# -V1.net
KiCad netlist of a schematic drawn in Altium Designer
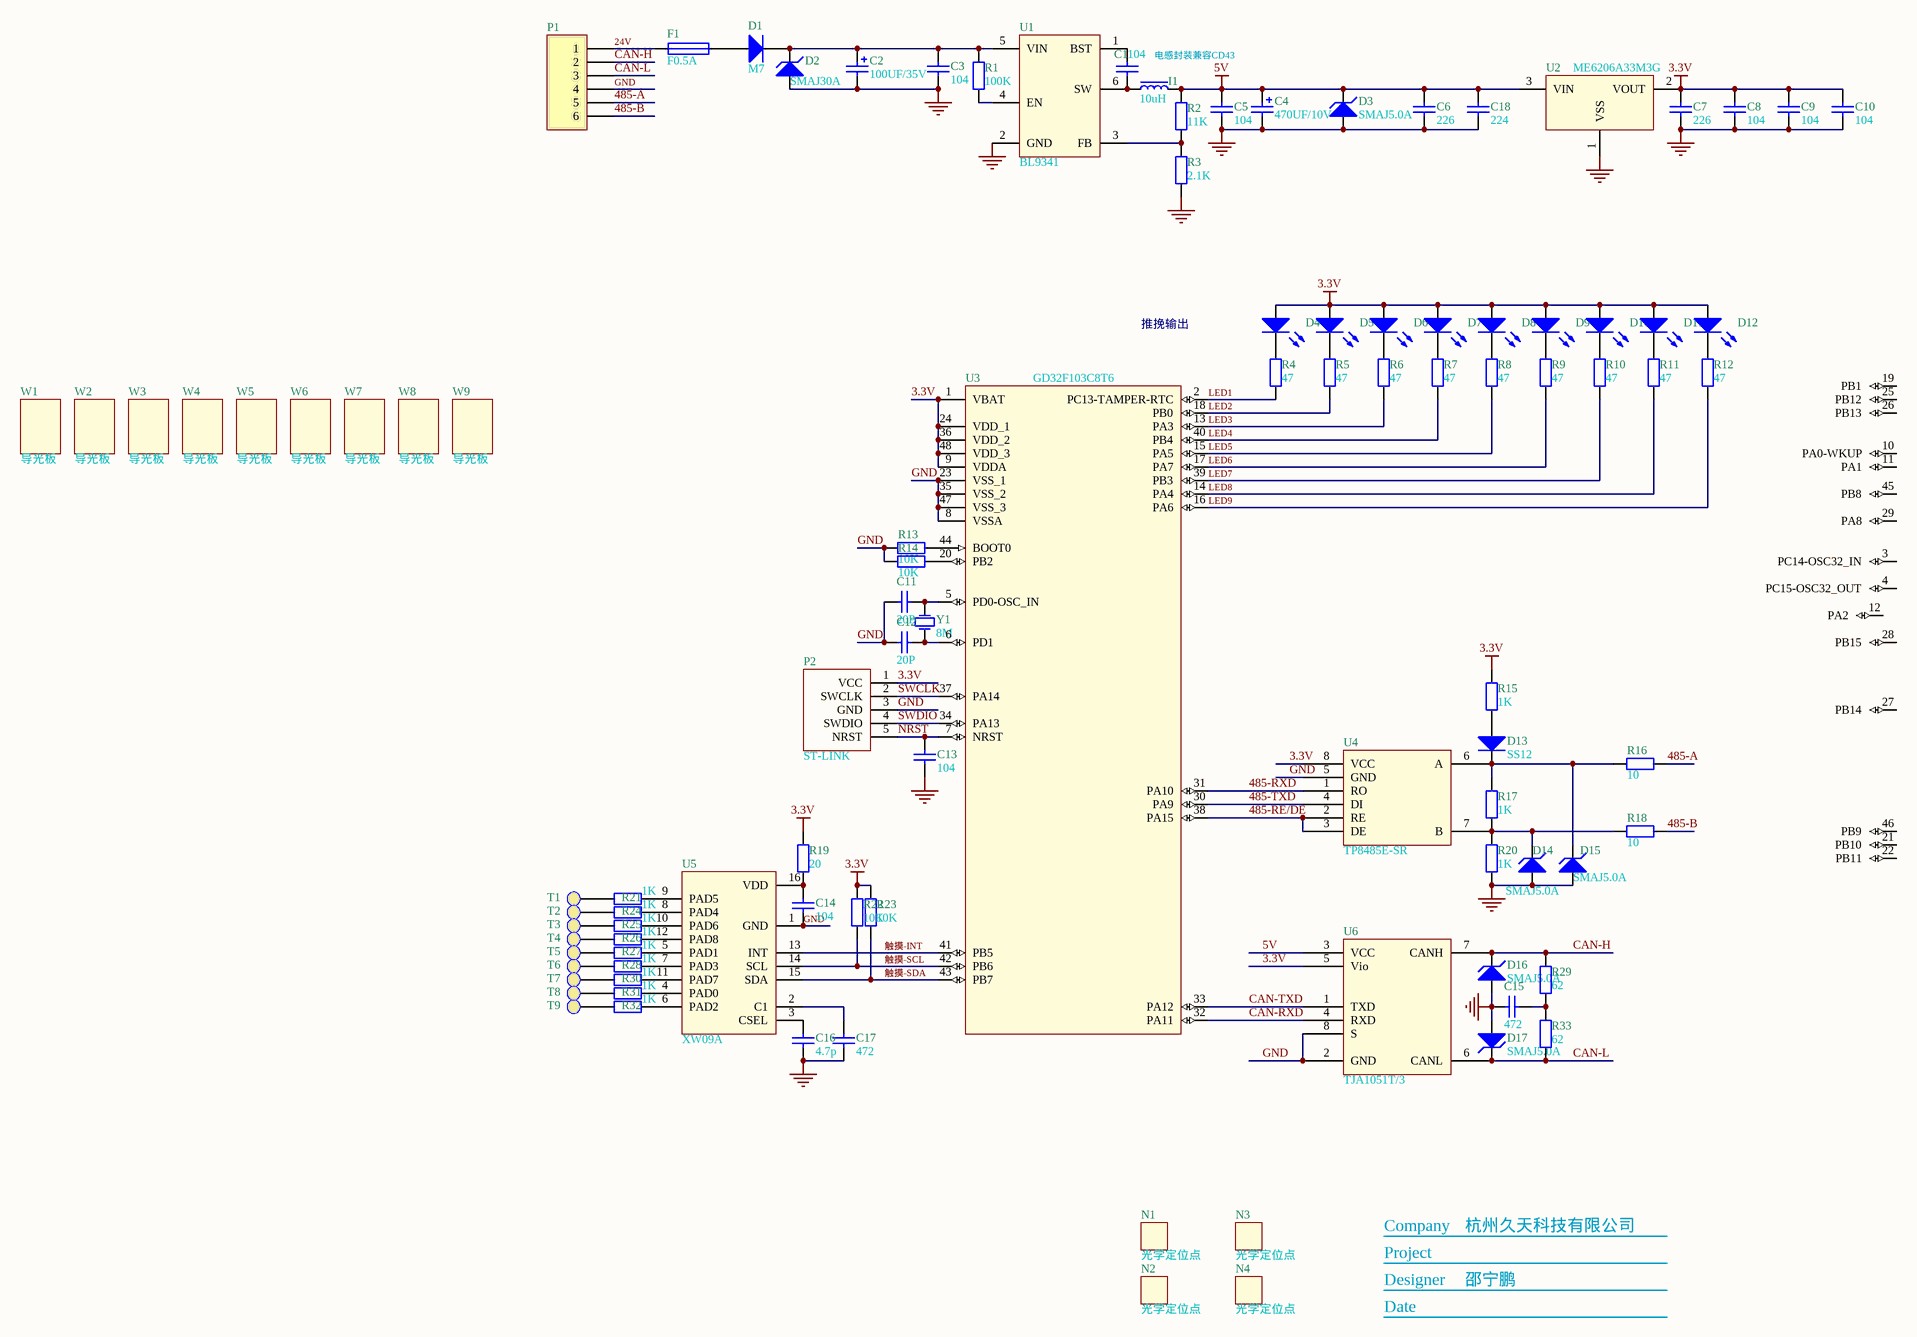
[diagram p0: 九键触摸面板-V1.SchDoc]

(export (version "E")
  (design (tool "Eeschema 10.0.6"))
  (components
    (comp (ref "C1")
      (value "104")
      (footprint "C-0603")
      (description "Capacitor")
      (fields (field (name "PUBLISHER") "Altium Limited"))
      (libsource (lib "元件2.0") (part "Cap"))
    )
    (comp (ref "C2")
      (value "100UF/35V")
      (footprint "贴片固态电容6.3*7.7")
      (description "Polarized Capacitor (Radial)")
      (fields (field (name "PUBLISHER") "Altium Limited"))
      (libsource (lib "元件2.0") (part "Cap Pol1"))
    )
    (comp (ref "C3")
      (value "104")
      (footprint "C-0603")
      (description "Capacitor")
      (fields (field (name "PUBLISHER") "Altium Limited"))
      (libsource (lib "元件2.0") (part "Cap"))
    )
    (comp (ref "C4")
      (value "470UF/10V")
      (footprint "贴片固态电容6.3*7.7")
      (description "Polarized Capacitor (Radial)")
      (fields (field (name "PUBLISHER") "Altium Limited"))
      (libsource (lib "元件2.0") (part "Cap Pol1"))
    )
    (comp (ref "C5")
      (value "104")
      (footprint "C-0603")
      (description "Capacitor")
      (fields (field (name "PUBLISHER") "Altium Limited"))
      (libsource (lib "元件2.0") (part "Cap"))
    )
    (comp (ref "C6")
      (value "226")
      (footprint "C-0603")
      (description "Capacitor")
      (fields (field (name "PUBLISHER") "Altium Limited"))
      (libsource (lib "元件2.0") (part "Cap"))
    )
    (comp (ref "C7")
      (value "226")
      (footprint "C-0603")
      (description "Capacitor")
      (fields (field (name "PUBLISHER") "Altium Limited"))
      (libsource (lib "元件2.0") (part "Cap"))
    )
    (comp (ref "C8")
      (value "104")
      (footprint "C-0603")
      (description "Capacitor")
      (fields (field (name "PUBLISHER") "Altium Limited"))
      (libsource (lib "元件2.0") (part "Cap"))
    )
    (comp (ref "C9")
      (value "104")
      (footprint "C-0603")
      (description "Capacitor")
      (fields (field (name "PUBLISHER") "Altium Limited"))
      (libsource (lib "元件2.0") (part "Cap"))
    )
    (comp (ref "C10")
      (value "104")
      (footprint "C-0603")
      (description "Capacitor")
      (fields (field (name "PUBLISHER") "Altium Limited"))
      (libsource (lib "元件2.0") (part "Cap"))
    )
    (comp (ref "C11")
      (value "20P")
      (footprint "C-0603")
      (description "0805")
      (fields (field (name "PUBLISHER") "Altium Limited"))
      (libsource (lib "2电容-V1.0") (part "Cap-0603"))
    )
    (comp (ref "C12")
      (value "20P")
      (footprint "C-0603")
      (description "0805")
      (fields (field (name "PUBLISHER") "Altium Limited"))
      (libsource (lib "2电容-V1.0") (part "Cap-0603"))
    )
    (comp (ref "C13")
      (value "104")
      (footprint "C-0603")
      (description "0805")
      (fields (field (name "PUBLISHER") "Altium Limited"))
      (libsource (lib "2电容-V1.0") (part "Cap-0603"))
    )
    (comp (ref "C14")
      (value "104")
      (footprint "C-0603")
      (description "0805")
      (fields (field (name "PUBLISHER") "Altium Limited"))
      (libsource (lib "2电容-V1.0") (part "Cap-0603"))
    )
    (comp (ref "C15")
      (value "472")
      (footprint "C-0603")
      (description "0805")
      (fields (field (name "PUBLISHER") "Altium Limited"))
      (libsource (lib "2电容-V1.0") (part "Cap-0603"))
    )
    (comp (ref "C16")
      (value "4.7p")
      (footprint "C-0603")
      (description "0805")
      (fields (field (name "PUBLISHER") "Altium Limited"))
      (libsource (lib "2电容-V1.0") (part "Cap-0603"))
    )
    (comp (ref "C17")
      (value "472")
      (footprint "C-0603")
      (description "0805")
      (fields (field (name "PUBLISHER") "Altium Limited"))
      (libsource (lib "2电容-V1.0") (part "Cap-0603"))
    )
    (comp (ref "C18")
      (value "224")
      (footprint "C-0603")
      (description "Capacitor")
      (fields (field (name "PUBLISHER") "Altium Limited"))
      (libsource (lib "元件2.0") (part "Cap"))
    )
    (comp (ref "D1")
      (value "M7")
      (footprint "SMA")
      (description "SMA")
      (fields (field (name "PUBLISHER") "Altium Limited"))
      (libsource (lib "4二极管-V1.1") (part "M7"))
    )
    (comp (ref "D2")
      (value "SMAJ30A")
      (footprint "SMA")
      (description "SMB")
      (libsource (lib "4二极管-V1.1") (part "TVS-1"))
    )
    (comp (ref "D3")
      (value "SMAJ5.0A")
      (footprint "SMA")
      (description "SMB")
      (libsource (lib "4二极管-V1.1") (part "TVS-1"))
    )
    (comp (ref "D4")
      (value "~")
      (footprint "LED-335侧面绿色-M")
      (fields (field (name "PUBLISHER") "Altium Limited"))
      (libsource (lib "4二极管-V1.1") (part "LED-0603-Blue"))
    )
    (comp (ref "D5")
      (value "~")
      (footprint "LED-335侧面绿色-M")
      (fields (field (name "PUBLISHER") "Altium Limited"))
      (libsource (lib "4二极管-V1.1") (part "LED-0603-Blue"))
    )
    (comp (ref "D6")
      (value "~")
      (footprint "LED-335侧面绿色-M")
      (fields (field (name "PUBLISHER") "Altium Limited"))
      (libsource (lib "4二极管-V1.1") (part "LED-0603-Blue"))
    )
    (comp (ref "D7")
      (value "~")
      (footprint "LED-335侧面绿色-M")
      (fields (field (name "PUBLISHER") "Altium Limited"))
      (libsource (lib "4二极管-V1.1") (part "LED-0603-Blue"))
    )
    (comp (ref "D8")
      (value "~")
      (footprint "LED-335侧面绿色-M")
      (fields (field (name "PUBLISHER") "Altium Limited"))
      (libsource (lib "4二极管-V1.1") (part "LED-0603-Blue"))
    )
    (comp (ref "D9")
      (value "~")
      (footprint "LED-335侧面绿色-M")
      (fields (field (name "PUBLISHER") "Altium Limited"))
      (libsource (lib "4二极管-V1.1") (part "LED-0603-Blue"))
    )
    (comp (ref "D10")
      (value "~")
      (footprint "LED-335侧面绿色-M")
      (fields (field (name "PUBLISHER") "Altium Limited"))
      (libsource (lib "4二极管-V1.1") (part "LED-0603-Blue"))
    )
    (comp (ref "D11")
      (value "~")
      (footprint "LED-335侧面绿色-M")
      (fields (field (name "PUBLISHER") "Altium Limited"))
      (libsource (lib "4二极管-V1.1") (part "LED-0603-Blue"))
    )
    (comp (ref "D12")
      (value "~")
      (footprint "LED-335侧面绿色-M")
      (fields (field (name "PUBLISHER") "Altium Limited"))
      (libsource (lib "4二极管-V1.1") (part "LED-0603-Blue"))
    )
    (comp (ref "D13")
      (value "SS12")
      (footprint "SMA")
      (description "SMA")
      (libsource (lib "4二极管-V1.1") (part "SS14"))
    )
    (comp (ref "D14")
      (value "SMAJ5.0A")
      (footprint "SMA")
      (description "SMB")
      (libsource (lib "4二极管-V1.1") (part "TVS-1"))
    )
    (comp (ref "D15")
      (value "SMAJ5.0A")
      (footprint "SMA")
      (description "SMB")
      (libsource (lib "4二极管-V1.1") (part "TVS-1"))
    )
    (comp (ref "D16")
      (value "SMAJ5.0A")
      (footprint "SMA")
      (description "SMB")
      (libsource (lib "4二极管-V1.1") (part "TVS-1"))
    )
    (comp (ref "D17")
      (value "SMAJ5.0A")
      (footprint "SMA")
      (description "SMB")
      (libsource (lib "4二极管-V1.1") (part "TVS-1"))
    )
    (comp (ref "F1")
      (value "F0.5A")
      (footprint "FUSE-1808")
      (description "Fuse")
      (fields (field (name "PUBLISHER") "Altium Limited"))
      (libsource (lib "11其他元件-V1.0") (part "Fuse 1"))
    )
    (comp (ref "I1") (value "10uH") (footprint "4030") (libsource (lib "3电感-V1.0") (part "Inductance3")))
    (comp (ref "N1") (value "光学定位点") (footprint "MARK-1mm-3mm") (libsource (lib "11其他元件-V1.0") (part "无引脚")))
    (comp (ref "N2") (value "光学定位点") (footprint "MARK-1mm-3mm") (libsource (lib "11其他元件-V1.0") (part "无引脚")))
    (comp (ref "N3") (value "光学定位点") (footprint "MARK-1mm-3mm") (libsource (lib "11其他元件-V1.0") (part "无引脚")))
    (comp (ref "N4") (value "光学定位点") (footprint "MARK-1mm-3mm") (libsource (lib "11其他元件-V1.0") (part "无引脚")))
    (comp (ref "P1")
      (value "~")
      (footprint "KF2EDG5.08V-6P-贴片")
      (description "Header, 6-Pin")
      (fields (field (name "PUBLISHER") "Altium Limited"))
      (libsource (lib "5排针-V1.0") (part "Header 6"))
    )
    (comp (ref "P2") (value "ST-LINK") (footprint "5P下载口") (libsource (lib "下载口") (part "ST-LINK-STM32")))
    (comp (ref "R1")
      (value "100K")
      (footprint "R-0603")
      (description "0603")
      (fields (field (name "PUBLISHER") "Altium Limited"))
      (libsource (lib "1电阻-V1.0") (part "Res2-0603"))
    )
    (comp (ref "R2")
      (value "11K")
      (footprint "R-0603")
      (description "0603")
      (fields (field (name "PUBLISHER") "Altium Limited"))
      (libsource (lib "1电阻-V1.0") (part "Res2-0603"))
    )
    (comp (ref "R3")
      (value "2.1K")
      (footprint "R-0603")
      (description "0603")
      (fields (field (name "PUBLISHER") "Altium Limited"))
      (libsource (lib "1电阻-V1.0") (part "Res2-0603"))
    )
    (comp (ref "R4")
      (value "47")
      (footprint "R-0603")
      (description "0603")
      (fields (field (name "PUBLISHER") "Altium Limited"))
      (libsource (lib "") (part "Res2-0603_1"))
    )
    (comp (ref "R5")
      (value "47")
      (footprint "R-0603")
      (description "0603")
      (fields (field (name "PUBLISHER") "Altium Limited"))
      (libsource (lib "") (part "Res2-0603_1"))
    )
    (comp (ref "R6")
      (value "47")
      (footprint "R-0603")
      (description "0603")
      (fields (field (name "PUBLISHER") "Altium Limited"))
      (libsource (lib "") (part "Res2-0603_1"))
    )
    (comp (ref "R7")
      (value "47")
      (footprint "R-0603")
      (description "0603")
      (fields (field (name "PUBLISHER") "Altium Limited"))
      (libsource (lib "") (part "Res2-0603_1"))
    )
    (comp (ref "R8")
      (value "47")
      (footprint "R-0603")
      (description "0603")
      (fields (field (name "PUBLISHER") "Altium Limited"))
      (libsource (lib "") (part "Res2-0603_1"))
    )
    (comp (ref "R9")
      (value "47")
      (footprint "R-0603")
      (description "0603")
      (fields (field (name "PUBLISHER") "Altium Limited"))
      (libsource (lib "") (part "Res2-0603_1"))
    )
    (comp (ref "R10")
      (value "47")
      (footprint "R-0603")
      (description "0603")
      (fields (field (name "PUBLISHER") "Altium Limited"))
      (libsource (lib "") (part "Res2-0603_1"))
    )
    (comp (ref "R11")
      (value "47")
      (footprint "R-0603")
      (description "0603")
      (fields (field (name "PUBLISHER") "Altium Limited"))
      (libsource (lib "") (part "Res2-0603_1"))
    )
    (comp (ref "R12")
      (value "47")
      (footprint "R-0603")
      (description "0603")
      (fields (field (name "PUBLISHER") "Altium Limited"))
      (libsource (lib "") (part "Res2-0603_1"))
    )
    (comp (ref "R13")
      (value "10K")
      (footprint "R-0603")
      (description "0603")
      (fields (field (name "PUBLISHER") "Altium Limited"))
      (libsource (lib "1电阻-V1.0") (part "Res2-0603"))
    )
    (comp (ref "R14")
      (value "10K")
      (footprint "R-0603")
      (description "0603")
      (fields (field (name "PUBLISHER") "Altium Limited"))
      (libsource (lib "1电阻-V1.0") (part "Res2-0603"))
    )
    (comp (ref "R15")
      (value "1K")
      (footprint "R-0603")
      (description "Resistor")
      (fields (field (name "PUBLISHER") "Altium Limited"))
      (libsource (lib "元件2.0") (part "Res2"))
    )
    (comp (ref "R16")
      (value "10")
      (footprint "R-0603")
      (description "Resistor")
      (fields (field (name "PUBLISHER") "Altium Limited"))
      (libsource (lib "Miscellaneous Devices") (part "Res2"))
    )
    (comp (ref "R17")
      (value "1K")
      (footprint "R-1206")
      (description "Resistor")
      (fields (field (name "PUBLISHER") "Altium Limited"))
      (libsource (lib "") (part "Res2_1"))
    )
    (comp (ref "R18")
      (value "10")
      (footprint "R-0603")
      (description "Resistor")
      (fields (field (name "PUBLISHER") "Altium Limited"))
      (libsource (lib "Miscellaneous Devices") (part "Res2"))
    )
    (comp (ref "R19")
      (value "20")
      (footprint "R-0603")
      (description "0603")
      (fields (field (name "PUBLISHER") "Altium Limited"))
      (libsource (lib "") (part "Res2-0603_1"))
    )
    (comp (ref "R20")
      (value "1K")
      (footprint "R-0603")
      (description "Resistor")
      (fields (field (name "PUBLISHER") "Altium Limited"))
      (libsource (lib "") (part "Res2_1"))
    )
    (comp (ref "R21")
      (value "1K")
      (footprint "R-0603")
      (description "0603")
      (fields (field (name "PUBLISHER") "Altium Limited"))
      (libsource (lib "1电阻-V1.0") (part "Res2-0603"))
    )
    (comp (ref "R22")
      (value "10K")
      (footprint "R-0603")
      (description "0603")
      (fields (field (name "PUBLISHER") "Altium Limited"))
      (libsource (lib "") (part "Res2-0603_2"))
    )
    (comp (ref "R23")
      (value "10K")
      (footprint "R-0603")
      (description "0603")
      (fields (field (name "PUBLISHER") "Altium Limited"))
      (libsource (lib "") (part "Res2-0603_2"))
    )
    (comp (ref "R24")
      (value "1K")
      (footprint "R-0603")
      (description "0603")
      (fields (field (name "PUBLISHER") "Altium Limited"))
      (libsource (lib "1电阻-V1.0") (part "Res2-0603"))
    )
    (comp (ref "R25")
      (value "1K")
      (footprint "R-0603")
      (description "0603")
      (fields (field (name "PUBLISHER") "Altium Limited"))
      (libsource (lib "1电阻-V1.0") (part "Res2-0603"))
    )
    (comp (ref "R26")
      (value "1K")
      (footprint "R-0603")
      (description "0603")
      (fields (field (name "PUBLISHER") "Altium Limited"))
      (libsource (lib "1电阻-V1.0") (part "Res2-0603"))
    )
    (comp (ref "R27")
      (value "1K")
      (footprint "R-0603")
      (description "0603")
      (fields (field (name "PUBLISHER") "Altium Limited"))
      (libsource (lib "1电阻-V1.0") (part "Res2-0603"))
    )
    (comp (ref "R28")
      (value "1K")
      (footprint "R-0603")
      (description "0603")
      (fields (field (name "PUBLISHER") "Altium Limited"))
      (libsource (lib "1电阻-V1.0") (part "Res2-0603"))
    )
    (comp (ref "R29")
      (value "62")
      (footprint "R-1206")
      (description "Resistor")
      (fields (field (name "PUBLISHER") "Altium Limited"))
      (libsource (lib "") (part "Res2_1"))
    )
    (comp (ref "R30")
      (value "1K")
      (footprint "R-0603")
      (description "0603")
      (fields (field (name "PUBLISHER") "Altium Limited"))
      (libsource (lib "1电阻-V1.0") (part "Res2-0603"))
    )
    (comp (ref "R31")
      (value "1K")
      (footprint "R-0603")
      (description "0603")
      (fields (field (name "PUBLISHER") "Altium Limited"))
      (libsource (lib "1电阻-V1.0") (part "Res2-0603"))
    )
    (comp (ref "R32")
      (value "1K")
      (footprint "R-0603")
      (description "0603")
      (fields (field (name "PUBLISHER") "Altium Limited"))
      (libsource (lib "1电阻-V1.0") (part "Res2-0603"))
    )
    (comp (ref "R33")
      (value "62")
      (footprint "R-1206")
      (description "Resistor")
      (fields (field (name "PUBLISHER") "Altium Limited"))
      (libsource (lib "") (part "Res2_1"))
    )
    (comp (ref "T1") (value "~") (footprint "焊点1mm") (libsource (lib "11其他元件-V1.0") (part "测试点")))
    (comp (ref "T2") (value "~") (footprint "焊点1mm") (libsource (lib "11其他元件-V1.0") (part "测试点")))
    (comp (ref "T3") (value "~") (footprint "焊点1mm") (libsource (lib "11其他元件-V1.0") (part "测试点")))
    (comp (ref "T4") (value "~") (footprint "焊点1mm") (libsource (lib "11其他元件-V1.0") (part "测试点")))
    (comp (ref "T5") (value "~") (footprint "焊点1mm") (libsource (lib "11其他元件-V1.0") (part "测试点")))
    (comp (ref "T6") (value "~") (footprint "焊点1mm") (libsource (lib "11其他元件-V1.0") (part "测试点")))
    (comp (ref "T7") (value "~") (footprint "焊点1mm") (libsource (lib "11其他元件-V1.0") (part "测试点")))
    (comp (ref "T8") (value "~") (footprint "焊点1mm") (libsource (lib "11其他元件-V1.0") (part "测试点")))
    (comp (ref "T9") (value "~") (footprint "焊点1mm") (libsource (lib "11其他元件-V1.0") (part "测试点")))
    (comp (ref "U1") (value "BL9341") (footprint "SOT-23-6-m") (libsource (lib "电源芯片DC-DC") (part "BL9341")))
    (comp (ref "U2")
      (value "ME6206A33M3G")
      (footprint "SOT-23")
      (description "LDO稳压 SOT-23")
      (libsource (lib "电源芯片-线性稳压-V1") (part "ME6206A33M3G"))
    )
    (comp (ref "U3")
      (value "GD32F103C8T6")
      (footprint "LQFP48-L")
      (libsource (lib "9单片机-V1.0") (part "GD32F103C8T6"))
    )
    (comp (ref "U4")
      (value "TP8485E-SR")
      (footprint "SOP-8-m")
      (description "RS485总线转串口")
      (libsource (lib "集成电路1.0") (part "MAX3082"))
    )
    (comp (ref "U5") (value "XW09A") (footprint "SOP-16-M") (libsource (lib "触摸-V1") (part "XW09A")))
    (comp (ref "U6") (value "TJA1051T/3") (footprint "SOP-8-M") (libsource (lib "通讯-V1") (part "TJA1051T/3")))
    (comp (ref "W1") (value "导光板") (footprint "导光板20.5*15*2") (libsource (lib "11其他元件-V1.0") (part "导光板")))
    (comp (ref "W2") (value "导光板") (footprint "导光板20.5*15*2") (libsource (lib "11其他元件-V1.0") (part "导光板")))
    (comp (ref "W3") (value "导光板") (footprint "导光板20.5*15*2") (libsource (lib "11其他元件-V1.0") (part "导光板")))
    (comp (ref "W4") (value "导光板") (footprint "导光板20.5*15*2") (libsource (lib "11其他元件-V1.0") (part "导光板")))
    (comp (ref "W5") (value "导光板") (footprint "导光板20.5*15*2") (libsource (lib "11其他元件-V1.0") (part "导光板")))
    (comp (ref "W6") (value "导光板") (footprint "导光板20.5*15*2") (libsource (lib "11其他元件-V1.0") (part "导光板")))
    (comp (ref "W7") (value "导光板") (footprint "导光板20.5*15*2") (libsource (lib "11其他元件-V1.0") (part "导光板")))
    (comp (ref "W8") (value "导光板") (footprint "导光板20.5*15*2") (libsource (lib "11其他元件-V1.0") (part "导光板")))
    (comp (ref "W9") (value "导光板") (footprint "导光板20.5*15*2") (libsource (lib "11其他元件-V1.0") (part "导光板")))
    (comp (ref "Y1") (value "8M") (footprint "HC-49SMD") (libsource (lib "11其他元件-V1.0") (part "晶振")))
  )
  (nets
    (net (code "1") (name "/24V") (class "Default")
      (node (ref "F1") (pin "1") (pinfunction "1_1") (pintype "passive"))
      (node (ref "P1") (pin "1") (pinfunction "1_1") (pintype "passive"))
    )
    (net (code "2") (name "/485-A") (class "Default")
      (node (ref "P1") (pin "5") (pinfunction "5_5") (pintype "passive"))
      (node (ref "R16") (pin "1") (pinfunction "1_1") (pintype "passive"))
    )
    (net (code "3") (name "/485-B") (class "Default")
      (node (ref "P1") (pin "6") (pinfunction "6_6") (pintype "passive"))
      (node (ref "R18") (pin "1") (pinfunction "1_1") (pintype "passive"))
    )
    (net (code "4") (name "/485-RE{slash}DE") (class "Default")
      (node (ref "U3") (pin "38") (pinfunction "PA15_38") (pintype "bidirectional"))
      (node (ref "U4") (pin "2") (pinfunction "RE_2") (pintype "passive"))
      (node (ref "U4") (pin "3") (pinfunction "DE_3") (pintype "passive"))
    )
    (net (code "5") (name "/485-RXD") (class "Default")
      (node (ref "U3") (pin "31") (pinfunction "PA10_31") (pintype "bidirectional"))
      (node (ref "U4") (pin "1") (pinfunction "RO_1") (pintype "passive"))
    )
    (net (code "6") (name "/485-TXD") (class "Default")
      (node (ref "U3") (pin "30") (pinfunction "PA9_30") (pintype "bidirectional"))
      (node (ref "U4") (pin "4") (pinfunction "DI_4") (pintype "passive"))
    )
    (net (code "7") (name "/CAN-H") (class "Default")
      (node (ref "D16") (pin "2") (pinfunction "K_2") (pintype "passive"))
      (node (ref "P1") (pin "2") (pinfunction "2_2") (pintype "passive"))
      (node (ref "R29") (pin "1") (pinfunction "1_1") (pintype "passive"))
      (node (ref "U6") (pin "7") (pinfunction "CANH_7") (pintype "passive"))
    )
    (net (code "8") (name "/CAN-L") (class "Default")
      (node (ref "D17") (pin "2") (pinfunction "K_2") (pintype "passive"))
      (node (ref "P1") (pin "3") (pinfunction "3_3") (pintype "passive"))
      (node (ref "R33") (pin "2") (pinfunction "2_2") (pintype "passive"))
      (node (ref "U6") (pin "6") (pinfunction "CANL_6") (pintype "passive"))
    )
    (net (code "9") (name "/CAN-RXD") (class "Default")
      (node (ref "U3") (pin "32") (pinfunction "PA11_32") (pintype "bidirectional"))
      (node (ref "U6") (pin "4") (pinfunction "RXD_4") (pintype "passive"))
    )
    (net (code "10") (name "/CAN-TXD") (class "Default")
      (node (ref "U3") (pin "33") (pinfunction "PA12_33") (pintype "bidirectional"))
      (node (ref "U6") (pin "1") (pinfunction "TXD_1") (pintype "passive"))
    )
    (net (code "11") (name "/LED1") (class "Default")
      (node (ref "R4") (pin "2") (pinfunction "2_2") (pintype "passive"))
      (node (ref "U3") (pin "2") (pinfunction "PC13-TAMPER-RTC_2") (pintype "bidirectional"))
    )
    (net (code "12") (name "/LED2") (class "Default")
      (node (ref "R5") (pin "2") (pinfunction "2_2") (pintype "passive"))
      (node (ref "U3") (pin "18") (pinfunction "PB0_18") (pintype "bidirectional"))
    )
    (net (code "13") (name "/LED3") (class "Default")
      (node (ref "R6") (pin "2") (pinfunction "2_2") (pintype "passive"))
      (node (ref "U3") (pin "13") (pinfunction "PA3_13") (pintype "bidirectional"))
    )
    (net (code "14") (name "/LED4") (class "Default")
      (node (ref "R7") (pin "2") (pinfunction "2_2") (pintype "passive"))
      (node (ref "U3") (pin "40") (pinfunction "PB4_40") (pintype "bidirectional"))
    )
    (net (code "15") (name "/LED5") (class "Default")
      (node (ref "R8") (pin "2") (pinfunction "2_2") (pintype "passive"))
      (node (ref "U3") (pin "15") (pinfunction "PA5_15") (pintype "bidirectional"))
    )
    (net (code "16") (name "/LED6") (class "Default")
      (node (ref "R9") (pin "2") (pinfunction "2_2") (pintype "passive"))
      (node (ref "U3") (pin "17") (pinfunction "PA7_17") (pintype "bidirectional"))
    )
    (net (code "17") (name "/LED7") (class "Default")
      (node (ref "R10") (pin "2") (pinfunction "2_2") (pintype "passive"))
      (node (ref "U3") (pin "39") (pinfunction "PB3_39") (pintype "bidirectional"))
    )
    (net (code "18") (name "/LED8") (class "Default")
      (node (ref "R11") (pin "2") (pinfunction "2_2") (pintype "passive"))
      (node (ref "U3") (pin "14") (pinfunction "PA4_14") (pintype "bidirectional"))
    )
    (net (code "19") (name "/LED9") (class "Default")
      (node (ref "R12") (pin "2") (pinfunction "2_2") (pintype "passive"))
      (node (ref "U3") (pin "16") (pinfunction "PA6_16") (pintype "bidirectional"))
    )
    (net (code "20") (name "/NRST") (class "Default")
      (node (ref "C13") (pin "2") (pinfunction "2_2") (pintype "passive"))
      (node (ref "P2") (pin "5") (pinfunction "NRST_5") (pintype "passive"))
      (node (ref "U3") (pin "7") (pinfunction "NRST_7") (pintype "bidirectional"))
    )
    (net (code "21") (name "/SWCLK") (class "Default")
      (node (ref "P2") (pin "2") (pinfunction "SWCLK_2") (pintype "passive"))
      (node (ref "U3") (pin "37") (pinfunction "PA14_37") (pintype "bidirectional"))
    )
    (net (code "22") (name "/SWDIO") (class "Default")
      (node (ref "P2") (pin "4") (pinfunction "SWDIO_4") (pintype "passive"))
      (node (ref "U3") (pin "34") (pinfunction "PA13_34") (pintype "bidirectional"))
    )
    (net (code "23") (name "/触摸-INT") (class "Default")
      (node (ref "U3") (pin "41") (pinfunction "PB5_41") (pintype "bidirectional"))
      (node (ref "U5") (pin "13") (pinfunction "INT_13") (pintype "passive"))
    )
    (net (code "24") (name "/触摸-SCL") (class "Default")
      (node (ref "R22") (pin "1") (pinfunction "1_1") (pintype "passive"))
      (node (ref "U3") (pin "42") (pinfunction "PB6_42") (pintype "bidirectional"))
      (node (ref "U5") (pin "14") (pinfunction "SCL_14") (pintype "passive"))
    )
    (net (code "25") (name "/触摸-SDA") (class "Default")
      (node (ref "R23") (pin "1") (pinfunction "1_1") (pintype "passive"))
      (node (ref "U3") (pin "43") (pinfunction "PB7_43") (pintype "bidirectional"))
      (node (ref "U5") (pin "15") (pinfunction "SDA_15") (pintype "passive"))
    )
    (net (code "26") (name "3.3V") (class "Default")
      (node (ref "C10") (pin "2") (pinfunction "2_2") (pintype "passive"))
      (node (ref "C7") (pin "2") (pinfunction "2_2") (pintype "passive"))
      (node (ref "C8") (pin "2") (pinfunction "2_2") (pintype "passive"))
      (node (ref "C9") (pin "2") (pinfunction "2_2") (pintype "passive"))
      (node (ref "D10") (pin "1") (pinfunction "A_1") (pintype "passive"))
      (node (ref "D11") (pin "1") (pinfunction "A_1") (pintype "passive"))
      (node (ref "D12") (pin "1") (pinfunction "A_1") (pintype "passive"))
      (node (ref "D4") (pin "1") (pinfunction "A_1") (pintype "passive"))
      (node (ref "D5") (pin "1") (pinfunction "A_1") (pintype "passive"))
      (node (ref "D6") (pin "1") (pinfunction "A_1") (pintype "passive"))
      (node (ref "D7") (pin "1") (pinfunction "A_1") (pintype "passive"))
      (node (ref "D8") (pin "1") (pinfunction "A_1") (pintype "passive"))
      (node (ref "D9") (pin "1") (pinfunction "A_1") (pintype "passive"))
      (node (ref "P2") (pin "1") (pinfunction "VCC_1") (pintype "passive"))
      (node (ref "R15") (pin "1") (pinfunction "1_1") (pintype "passive"))
      (node (ref "R19") (pin "1") (pinfunction "1_1") (pintype "passive"))
      (node (ref "R22") (pin "2") (pinfunction "2_2") (pintype "passive"))
      (node (ref "R23") (pin "2") (pinfunction "2_2") (pintype "passive"))
      (node (ref "U2") (pin "2") (pinfunction "VOUT_2") (pintype "passive"))
      (node (ref "U3") (pin "1") (pinfunction "VBAT_1") (pintype "power_in"))
      (node (ref "U3") (pin "24") (pinfunction "VDD_1_24") (pintype "power_in"))
      (node (ref "U3") (pin "36") (pinfunction "VDD_2_36") (pintype "power_in"))
      (node (ref "U3") (pin "48") (pinfunction "VDD_3_48") (pintype "power_in"))
      (node (ref "U3") (pin "9") (pinfunction "VDDA_9") (pintype "power_in"))
      (node (ref "U4") (pin "8") (pinfunction "VCC_8") (pintype "passive"))
      (node (ref "U6") (pin "5") (pinfunction "Vio_5") (pintype "passive"))
    )
    (net (code "27") (name "5V") (class "Default")
      (node (ref "C18") (pin "2") (pinfunction "2_2") (pintype "passive"))
      (node (ref "C4") (pin "1") (pinfunction "1_1") (pintype "passive"))
      (node (ref "C5") (pin "2") (pinfunction "2_2") (pintype "passive"))
      (node (ref "C6") (pin "2") (pinfunction "2_2") (pintype "passive"))
      (node (ref "D3") (pin "2") (pinfunction "K_2") (pintype "passive"))
      (node (ref "I1") (pin "2") (pinfunction "2_2") (pintype "passive"))
      (node (ref "R2") (pin "1") (pinfunction "1_1") (pintype "passive"))
      (node (ref "U2") (pin "3") (pinfunction "VIN_3") (pintype "passive"))
      (node (ref "U6") (pin "3") (pinfunction "VCC_3") (pintype "passive"))
    )
    (net (code "28") (name "GND") (class "Default")
      (node (ref "C10") (pin "1") (pinfunction "1_1") (pintype "passive"))
      (node (ref "C11") (pin "1") (pinfunction "1_1") (pintype "passive"))
      (node (ref "C12") (pin "1") (pinfunction "1_1") (pintype "passive"))
      (node (ref "C13") (pin "1") (pinfunction "1_1") (pintype "passive"))
      (node (ref "C14") (pin "1") (pinfunction "1_1") (pintype "passive"))
      (node (ref "C15") (pin "1") (pinfunction "1_1") (pintype "passive"))
      (node (ref "C16") (pin "1") (pinfunction "1_1") (pintype "passive"))
      (node (ref "C17") (pin "1") (pinfunction "1_1") (pintype "passive"))
      (node (ref "C18") (pin "1") (pinfunction "1_1") (pintype "passive"))
      (node (ref "C2") (pin "2") (pinfunction "2_2") (pintype "passive"))
      (node (ref "C3") (pin "1") (pinfunction "1_1") (pintype "passive"))
      (node (ref "C4") (pin "2") (pinfunction "2_2") (pintype "passive"))
      (node (ref "C5") (pin "1") (pinfunction "1_1") (pintype "passive"))
      (node (ref "C6") (pin "1") (pinfunction "1_1") (pintype "passive"))
      (node (ref "C7") (pin "1") (pinfunction "1_1") (pintype "passive"))
      (node (ref "C8") (pin "1") (pinfunction "1_1") (pintype "passive"))
      (node (ref "C9") (pin "1") (pinfunction "1_1") (pintype "passive"))
      (node (ref "D14") (pin "1") (pinfunction "A_1") (pintype "passive"))
      (node (ref "D15") (pin "1") (pinfunction "A_1") (pintype "passive"))
      (node (ref "D16") (pin "1") (pinfunction "A_1") (pintype "passive"))
      (node (ref "D17") (pin "1") (pinfunction "A_1") (pintype "passive"))
      (node (ref "D2") (pin "1") (pinfunction "A_1") (pintype "passive"))
      (node (ref "D3") (pin "1") (pinfunction "A_1") (pintype "passive"))
      (node (ref "P1") (pin "4") (pinfunction "4_4") (pintype "passive"))
      (node (ref "P2") (pin "3") (pinfunction "GND_3") (pintype "passive"))
      (node (ref "R13") (pin "2") (pinfunction "2_2") (pintype "passive"))
      (node (ref "R14") (pin "2") (pinfunction "2_2") (pintype "passive"))
      (node (ref "R20") (pin "1") (pinfunction "1_1") (pintype "passive"))
      (node (ref "R3") (pin "2") (pinfunction "2_2") (pintype "passive"))
      (node (ref "U1") (pin "2") (pinfunction "GND_2") (pintype "passive"))
      (node (ref "U2") (pin "1") (pinfunction "VSS_1") (pintype "passive"))
      (node (ref "U3") (pin "23") (pinfunction "VSS_1_23") (pintype "power_in"))
      (node (ref "U3") (pin "35") (pinfunction "VSS_2_35") (pintype "power_in"))
      (node (ref "U3") (pin "47") (pinfunction "VSS_3_47") (pintype "power_in"))
      (node (ref "U3") (pin "8") (pinfunction "VSSA_8") (pintype "power_in"))
      (node (ref "U4") (pin "5") (pinfunction "GND_5") (pintype "passive"))
      (node (ref "U5") (pin "1") (pinfunction "GND_1") (pintype "passive"))
      (node (ref "U6") (pin "2") (pinfunction "GND_2") (pintype "passive"))
      (node (ref "U6") (pin "8") (pinfunction "S_8") (pintype "passive"))
    )
    (net (code "29") (name "Net-(C15-Pad2)") (class "Default")
      (node (ref "C15") (pin "2") (pinfunction "2_2") (pintype "passive"))
      (node (ref "R29") (pin "2") (pinfunction "2_2") (pintype "passive"))
      (node (ref "R33") (pin "1") (pinfunction "1_1") (pintype "passive"))
    )
    (net (code "30") (name "Net-(D1-A)") (class "Default")
      (node (ref "D1") (pin "1") (pinfunction "A_1") (pintype "passive"))
      (node (ref "F1") (pin "2") (pinfunction "2_2") (pintype "passive"))
    )
    (net (code "31") (name "Net-(D1-K)") (class "Default")
      (node (ref "C2") (pin "1") (pinfunction "1_1") (pintype "passive"))
      (node (ref "C3") (pin "2") (pinfunction "2_2") (pintype "passive"))
      (node (ref "D1") (pin "2") (pinfunction "K_2") (pintype "passive"))
      (node (ref "D2") (pin "2") (pinfunction "K_2") (pintype "passive"))
      (node (ref "R1") (pin "1") (pinfunction "1_1") (pintype "passive"))
      (node (ref "U1") (pin "5") (pinfunction "VIN_5") (pintype "passive"))
    )
    (net (code "32") (name "Net-(D4-K)") (class "Default")
      (node (ref "D4") (pin "2") (pinfunction "K_2") (pintype "passive"))
      (node (ref "R4") (pin "1") (pinfunction "1_1") (pintype "passive"))
    )
    (net (code "33") (name "Net-(D5-K)") (class "Default")
      (node (ref "D5") (pin "2") (pinfunction "K_2") (pintype "passive"))
      (node (ref "R5") (pin "1") (pinfunction "1_1") (pintype "passive"))
    )
    (net (code "34") (name "Net-(D6-K)") (class "Default")
      (node (ref "D6") (pin "2") (pinfunction "K_2") (pintype "passive"))
      (node (ref "R6") (pin "1") (pinfunction "1_1") (pintype "passive"))
    )
    (net (code "35") (name "Net-(D7-K)") (class "Default")
      (node (ref "D7") (pin "2") (pinfunction "K_2") (pintype "passive"))
      (node (ref "R7") (pin "1") (pinfunction "1_1") (pintype "passive"))
    )
    (net (code "36") (name "Net-(D8-K)") (class "Default")
      (node (ref "D8") (pin "2") (pinfunction "K_2") (pintype "passive"))
      (node (ref "R8") (pin "1") (pinfunction "1_1") (pintype "passive"))
    )
    (net (code "37") (name "Net-(D9-K)") (class "Default")
      (node (ref "D9") (pin "2") (pinfunction "K_2") (pintype "passive"))
      (node (ref "R9") (pin "1") (pinfunction "1_1") (pintype "passive"))
    )
    (net (code "38") (name "Net-(D10-K)") (class "Default")
      (node (ref "D10") (pin "2") (pinfunction "K_2") (pintype "passive"))
      (node (ref "R10") (pin "1") (pinfunction "1_1") (pintype "passive"))
    )
    (net (code "39") (name "Net-(D11-K)") (class "Default")
      (node (ref "D11") (pin "2") (pinfunction "K_2") (pintype "passive"))
      (node (ref "R11") (pin "1") (pinfunction "1_1") (pintype "passive"))
    )
    (net (code "40") (name "Net-(D12-K)") (class "Default")
      (node (ref "D12") (pin "2") (pinfunction "K_2") (pintype "passive"))
      (node (ref "R12") (pin "1") (pinfunction "1_1") (pintype "passive"))
    )
    (net (code "41") (name "Net-(D13-A)") (class "Default")
      (node (ref "D13") (pin "1") (pinfunction "A_1") (pintype "passive"))
      (node (ref "R15") (pin "2") (pinfunction "2_2") (pintype "passive"))
    )
    (net (code "42") (name "Net-(D13-K)") (class "Default")
      (node (ref "D13") (pin "2") (pinfunction "K_2") (pintype "passive"))
      (node (ref "D15") (pin "2") (pinfunction "K_2") (pintype "passive"))
      (node (ref "R16") (pin "2") (pinfunction "2_2") (pintype "passive"))
      (node (ref "R17") (pin "1") (pinfunction "1_1") (pintype "passive"))
      (node (ref "U4") (pin "6") (pinfunction "A_6") (pintype "passive"))
    )
    (net (code "43") (name "Net-(D14-K)") (class "Default")
      (node (ref "D14") (pin "2") (pinfunction "K_2") (pintype "passive"))
      (node (ref "R17") (pin "2") (pinfunction "2_2") (pintype "passive"))
      (node (ref "R18") (pin "2") (pinfunction "2_2") (pintype "passive"))
      (node (ref "R20") (pin "2") (pinfunction "2_2") (pintype "passive"))
      (node (ref "U4") (pin "7") (pinfunction "B_7") (pintype "passive"))
    )
    (net (code "44") (name "Net-(R21-Pad2)") (class "Default")
      (node (ref "R21") (pin "2") (pinfunction "2_2") (pintype "passive"))
      (node (ref "T1") (pin "1") (pinfunction "1_1") (pintype "passive"))
    )
    (net (code "45") (name "Net-(R24-Pad2)") (class "Default")
      (node (ref "R24") (pin "2") (pinfunction "2_2") (pintype "passive"))
      (node (ref "T2") (pin "1") (pinfunction "1_1") (pintype "passive"))
    )
    (net (code "46") (name "Net-(R25-Pad2)") (class "Default")
      (node (ref "R25") (pin "2") (pinfunction "2_2") (pintype "passive"))
      (node (ref "T3") (pin "1") (pinfunction "1_1") (pintype "passive"))
    )
    (net (code "47") (name "Net-(R26-Pad2)") (class "Default")
      (node (ref "R26") (pin "2") (pinfunction "2_2") (pintype "passive"))
      (node (ref "T4") (pin "1") (pinfunction "1_1") (pintype "passive"))
    )
    (net (code "48") (name "Net-(R27-Pad2)") (class "Default")
      (node (ref "R27") (pin "2") (pinfunction "2_2") (pintype "passive"))
      (node (ref "T5") (pin "1") (pinfunction "1_1") (pintype "passive"))
    )
    (net (code "49") (name "Net-(R28-Pad2)") (class "Default")
      (node (ref "R28") (pin "2") (pinfunction "2_2") (pintype "passive"))
      (node (ref "T6") (pin "1") (pinfunction "1_1") (pintype "passive"))
    )
    (net (code "50") (name "Net-(R30-Pad2)") (class "Default")
      (node (ref "R30") (pin "2") (pinfunction "2_2") (pintype "passive"))
      (node (ref "T7") (pin "1") (pinfunction "1_1") (pintype "passive"))
    )
    (net (code "51") (name "Net-(R31-Pad2)") (class "Default")
      (node (ref "R31") (pin "2") (pinfunction "2_2") (pintype "passive"))
      (node (ref "T8") (pin "1") (pinfunction "1_1") (pintype "passive"))
    )
    (net (code "52") (name "Net-(R32-Pad2)") (class "Default")
      (node (ref "R32") (pin "2") (pinfunction "2_2") (pintype "passive"))
      (node (ref "T9") (pin "1") (pinfunction "1_1") (pintype "passive"))
    )
    (net (code "53") (name "Net-(U1-BST)") (class "Default")
      (node (ref "C1") (pin "2") (pinfunction "2_2") (pintype "passive"))
      (node (ref "U1") (pin "1") (pinfunction "BST_1") (pintype "passive"))
    )
    (net (code "54") (name "Net-(U1-EN)") (class "Default")
      (node (ref "R1") (pin "2") (pinfunction "2_2") (pintype "passive"))
      (node (ref "U1") (pin "4") (pinfunction "EN_4") (pintype "passive"))
    )
    (net (code "55") (name "Net-(U1-FB)") (class "Default")
      (node (ref "R2") (pin "2") (pinfunction "2_2") (pintype "passive"))
      (node (ref "R3") (pin "1") (pinfunction "1_1") (pintype "passive"))
      (node (ref "U1") (pin "3") (pinfunction "FB_3") (pintype "passive"))
    )
    (net (code "56") (name "Net-(U1-SW)") (class "Default")
      (node (ref "C1") (pin "1") (pinfunction "1_1") (pintype "passive"))
      (node (ref "I1") (pin "1") (pinfunction "1_1") (pintype "passive"))
      (node (ref "U1") (pin "6") (pinfunction "SW_6") (pintype "passive"))
    )
    (net (code "57") (name "Net-(U3-BOOT0)") (class "Default")
      (node (ref "R13") (pin "1") (pinfunction "1_1") (pintype "passive"))
      (node (ref "U3") (pin "44") (pinfunction "BOOT0_44") (pintype "input"))
    )
    (net (code "58") (name "Net-(U3-PB2)") (class "Default")
      (node (ref "R14") (pin "1") (pinfunction "1_1") (pintype "passive"))
      (node (ref "U3") (pin "20") (pinfunction "PB2_20") (pintype "bidirectional"))
    )
    (net (code "59") (name "Net-(U3-PD0-OSC_IN)") (class "Default")
      (node (ref "C11") (pin "2") (pinfunction "2_2") (pintype "passive"))
      (node (ref "U3") (pin "5") (pinfunction "PD0-OSC_IN_5") (pintype "bidirectional"))
      (node (ref "Y1") (pin "2") (pinfunction "OSC2_2") (pintype "passive"))
    )
    (net (code "60") (name "Net-(U3-PD1)") (class "Default")
      (node (ref "C12") (pin "2") (pinfunction "2_2") (pintype "passive"))
      (node (ref "U3") (pin "6") (pinfunction "PD1_6") (pintype "bidirectional"))
      (node (ref "Y1") (pin "1") (pinfunction "OSC1_1") (pintype "passive"))
    )
    (net (code "61") (name "Net-(U5-C1)") (class "Default")
      (node (ref "C17") (pin "2") (pinfunction "2_2") (pintype "passive"))
      (node (ref "U5") (pin "2") (pinfunction "C1_2") (pintype "passive"))
    )
    (net (code "62") (name "Net-(U5-CSEL)") (class "Default")
      (node (ref "C16") (pin "2") (pinfunction "2_2") (pintype "passive"))
      (node (ref "U5") (pin "3") (pinfunction "CSEL_3") (pintype "passive"))
    )
    (net (code "63") (name "Net-(U5-PAD0)") (class "Default")
      (node (ref "R31") (pin "1") (pinfunction "1_1") (pintype "passive"))
      (node (ref "U5") (pin "4") (pinfunction "PAD0_4") (pintype "passive"))
    )
    (net (code "64") (name "Net-(U5-PAD1)") (class "Default")
      (node (ref "R27") (pin "1") (pinfunction "1_1") (pintype "passive"))
      (node (ref "U5") (pin "5") (pinfunction "PAD1_5") (pintype "passive"))
    )
    (net (code "65") (name "Net-(U5-PAD2)") (class "Default")
      (node (ref "R32") (pin "1") (pinfunction "1_1") (pintype "passive"))
      (node (ref "U5") (pin "6") (pinfunction "PAD2_6") (pintype "passive"))
    )
    (net (code "66") (name "Net-(U5-PAD3)") (class "Default")
      (node (ref "R28") (pin "1") (pinfunction "1_1") (pintype "passive"))
      (node (ref "U5") (pin "7") (pinfunction "PAD3_7") (pintype "passive"))
    )
    (net (code "67") (name "Net-(U5-PAD4)") (class "Default")
      (node (ref "R24") (pin "1") (pinfunction "1_1") (pintype "passive"))
      (node (ref "U5") (pin "8") (pinfunction "PAD4_8") (pintype "passive"))
    )
    (net (code "68") (name "Net-(U5-PAD5)") (class "Default")
      (node (ref "R21") (pin "1") (pinfunction "1_1") (pintype "passive"))
      (node (ref "U5") (pin "9") (pinfunction "PAD5_9") (pintype "passive"))
    )
    (net (code "69") (name "Net-(U5-PAD6)") (class "Default")
      (node (ref "R25") (pin "1") (pinfunction "1_1") (pintype "passive"))
      (node (ref "U5") (pin "10") (pinfunction "PAD6_10") (pintype "passive"))
    )
    (net (code "70") (name "Net-(U5-PAD7)") (class "Default")
      (node (ref "R30") (pin "1") (pinfunction "1_1") (pintype "passive"))
      (node (ref "U5") (pin "11") (pinfunction "PAD7_11") (pintype "passive"))
    )
    (net (code "71") (name "Net-(U5-PAD8)") (class "Default")
      (node (ref "R26") (pin "1") (pinfunction "1_1") (pintype "passive"))
      (node (ref "U5") (pin "12") (pinfunction "PAD8_12") (pintype "passive"))
    )
    (net (code "72") (name "Net-(U5-VDD)") (class "Default")
      (node (ref "C14") (pin "2") (pinfunction "2_2") (pintype "passive"))
      (node (ref "R19") (pin "2") (pinfunction "2_2") (pintype "passive"))
      (node (ref "U5") (pin "16") (pinfunction "VDD_16") (pintype "passive"))
    )
    (net (code "73") (name "unconnected-(U3-PA0-WKUP-Pad10)") (class "Default")
      (node (ref "U3") (pin "10") (pinfunction "PA0-WKUP_10") (pintype "bidirectional"))
    )
    (net (code "74") (name "unconnected-(U3-PA1-Pad11)") (class "Default")
      (node (ref "U3") (pin "11") (pinfunction "PA1_11") (pintype "bidirectional"))
    )
    (net (code "75") (name "unconnected-(U3-PA2-Pad12)") (class "Default")
      (node (ref "U3") (pin "12") (pinfunction "PA2_12") (pintype "bidirectional"))
    )
    (net (code "76") (name "unconnected-(U3-PA8-Pad29)") (class "Default")
      (node (ref "U3") (pin "29") (pinfunction "PA8_29") (pintype "bidirectional"))
    )
    (net (code "77") (name "unconnected-(U3-PB1-Pad19)") (class "Default")
      (node (ref "U3") (pin "19") (pinfunction "PB1_19") (pintype "bidirectional"))
    )
    (net (code "78") (name "unconnected-(U3-PB8-Pad45)") (class "Default")
      (node (ref "U3") (pin "45") (pinfunction "PB8_45") (pintype "bidirectional"))
    )
    (net (code "79") (name "unconnected-(U3-PB9-Pad46)") (class "Default")
      (node (ref "U3") (pin "46") (pinfunction "PB9_46") (pintype "bidirectional"))
    )
    (net (code "80") (name "unconnected-(U3-PB10-Pad21)") (class "Default")
      (node (ref "U3") (pin "21") (pinfunction "PB10_21") (pintype "bidirectional"))
    )
    (net (code "81") (name "unconnected-(U3-PB11-Pad22)") (class "Default")
      (node (ref "U3") (pin "22") (pinfunction "PB11_22") (pintype "bidirectional"))
    )
    (net (code "82") (name "unconnected-(U3-PB12-Pad25)") (class "Default")
      (node (ref "U3") (pin "25") (pinfunction "PB12_25") (pintype "bidirectional"))
    )
    (net (code "83") (name "unconnected-(U3-PB13-Pad26)") (class "Default")
      (node (ref "U3") (pin "26") (pinfunction "PB13_26") (pintype "bidirectional"))
    )
    (net (code "84") (name "unconnected-(U3-PB14-Pad27)") (class "Default")
      (node (ref "U3") (pin "27") (pinfunction "PB14_27") (pintype "bidirectional"))
    )
    (net (code "85") (name "unconnected-(U3-PB15-Pad28)") (class "Default")
      (node (ref "U3") (pin "28") (pinfunction "PB15_28") (pintype "bidirectional"))
    )
    (net (code "86") (name "unconnected-(U3-PC14-OSC32_IN-Pad3)") (class "Default")
      (node (ref "U3") (pin "3") (pinfunction "PC14-OSC32_IN_3") (pintype "bidirectional"))
    )
    (net (code "87") (name "unconnected-(U3-PC15-OSC32_OUT-Pad4)") (class "Default")
      (node (ref "U3") (pin "4") (pinfunction "PC15-OSC32_OUT_4") (pintype "bidirectional"))
    )
  )
)
